# P05_Processor_Page_3_of_3.net
KiCad netlist of a schematic drawn in Altium Designer
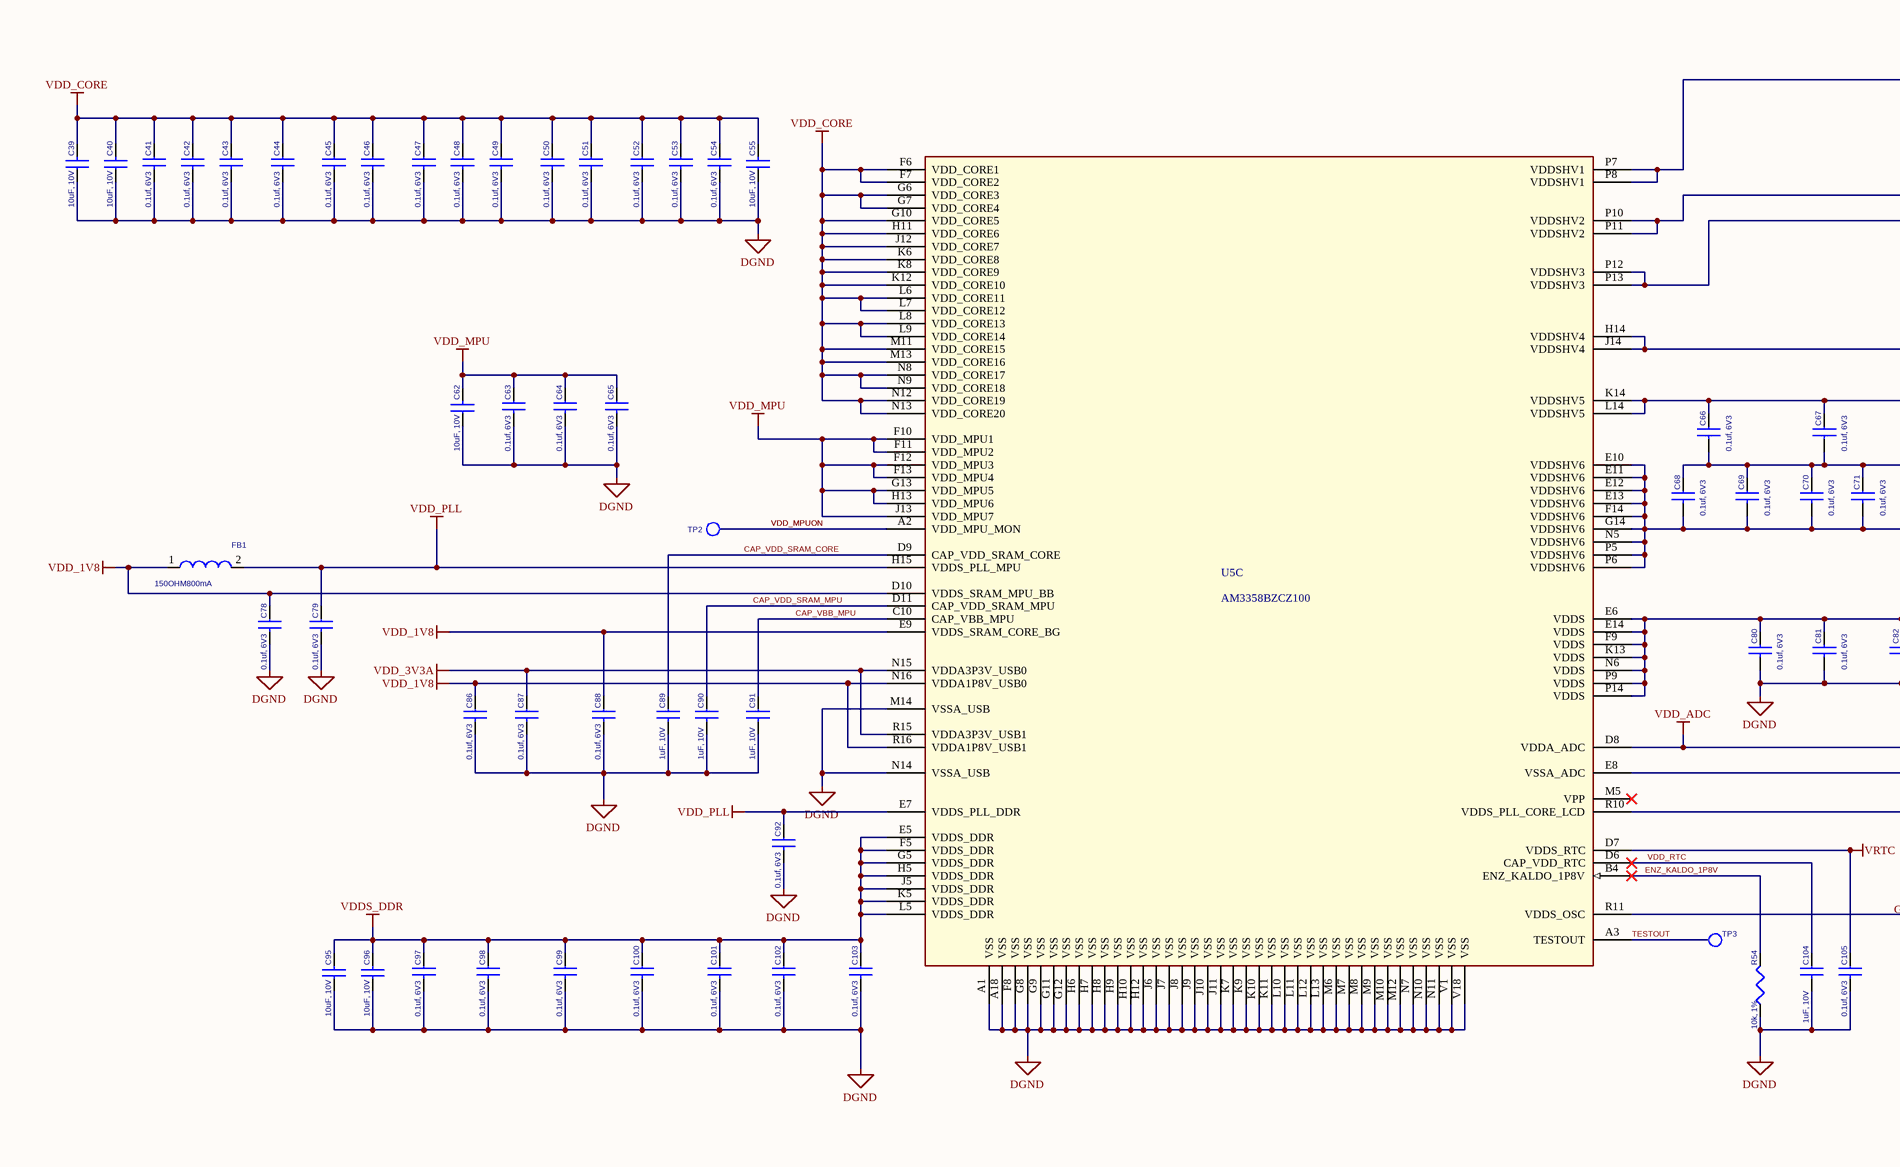
[diagram p0: P05_Processor Page 3 of 3.SchDoc, left]
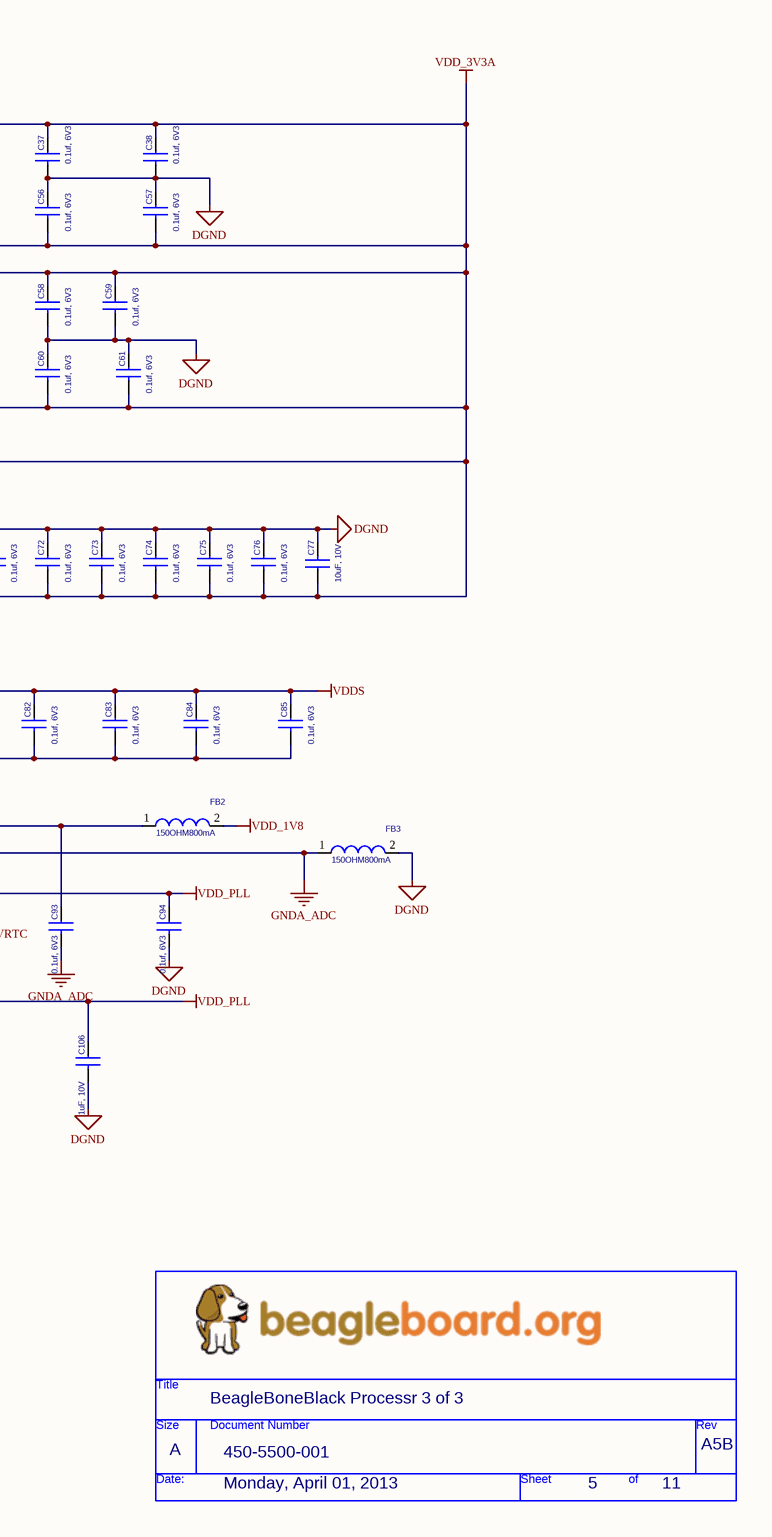
[diagram p1: P05_Processor Page 3 of 3.SchDoc, right]

(export (version "E")
  (design (tool "Eeschema 10.0.6"))
  (components
    (comp (ref "C37")
      (value "0.1uf, 6V3")
      (footprint "402")
      (description "CAP CER 0.1UF 6.3V 10% X5R 0402")
      (fields
        (field (name "MANUFACTURER") "TDK Corporation")
        (field (name "MANUFACTURER PART NUMBER") "C1005X5R0J104K050BA")
      )
      (libsource (lib "BEAGLEBONEBLACK_REV A5B") (part "CAP_0.1uF_X7R_16V_10% 0402"))
    )
    (comp (ref "C38")
      (value "0.1uf, 6V3")
      (footprint "402")
      (description "CAP CER 0.1UF 6.3V 10% X5R 0402")
      (fields
        (field (name "MANUFACTURER") "TDK Corporation")
        (field (name "MANUFACTURER PART NUMBER") "C1005X5R0J104K050BA")
      )
      (libsource (lib "BEAGLEBONEBLACK_REV A5B") (part "CAP_0.1uF_X7R_16V_10% 0402"))
    )
    (comp (ref "C39")
      (value "10uF, 10V")
      (description "CAP CER 10UF 10V Y5V 0805")
      (fields
        (field (name "MANUFACTURER") "TDK Corporation")
        (field (name "MANUFACTURER PART NUMBER") "C2012Y5V1A106Z")
      )
      (libsource (lib "BEAGLEBONEBLACK_REV A5B") (part "CAP_10uF_Y5V_10V_10%_0805"))
    )
    (comp (ref "C40")
      (value "10uF, 10V")
      (description "CAP CER 10UF 10V Y5V 0805")
      (fields
        (field (name "MANUFACTURER") "TDK Corporation")
        (field (name "MANUFACTURER PART NUMBER") "C2012Y5V1A106Z")
      )
      (libsource (lib "BEAGLEBONEBLACK_REV A5B") (part "CAP_10uF_Y5V_10V_10%_0805"))
    )
    (comp (ref "C41")
      (value "0.1uf, 6V3")
      (footprint "402")
      (description "CAP CER 0.1UF 6.3V 10% X5R 0402")
      (fields
        (field (name "MANUFACTURER") "TDK Corporation")
        (field (name "MANUFACTURER PART NUMBER") "C1005X5R0J104K050BA")
      )
      (libsource (lib "BEAGLEBONEBLACK_REV A5B") (part "CAP_0.1uF_X7R_16V_10% 0402"))
    )
    (comp (ref "C42")
      (value "0.1uf, 6V3")
      (footprint "402")
      (description "CAP CER 0.1UF 6.3V 10% X5R 0402")
      (fields
        (field (name "MANUFACTURER") "TDK Corporation")
        (field (name "MANUFACTURER PART NUMBER") "C1005X5R0J104K050BA")
      )
      (libsource (lib "BEAGLEBONEBLACK_REV A5B") (part "CAP_0.1uF_X7R_16V_10% 0402"))
    )
    (comp (ref "C43")
      (value "0.1uf, 6V3")
      (footprint "402")
      (description "CAP CER 0.1UF 6.3V 10% X5R 0402")
      (fields
        (field (name "MANUFACTURER") "TDK Corporation")
        (field (name "MANUFACTURER PART NUMBER") "C1005X5R0J104K050BA")
      )
      (libsource (lib "BEAGLEBONEBLACK_REV A5B") (part "CAP_0.1uF_X7R_16V_10% 0402"))
    )
    (comp (ref "C44")
      (value "0.1uf, 6V3")
      (footprint "402")
      (description "CAP CER 0.1UF 6.3V 10% X5R 0402")
      (fields
        (field (name "MANUFACTURER") "TDK Corporation")
        (field (name "MANUFACTURER PART NUMBER") "C1005X5R0J104K050BA")
      )
      (libsource (lib "BEAGLEBONEBLACK_REV A5B") (part "CAP_0.1uF_X7R_16V_10% 0402"))
    )
    (comp (ref "C45")
      (value "0.1uf, 6V3")
      (footprint "402")
      (description "CAP CER 0.1UF 6.3V 10% X5R 0402")
      (fields
        (field (name "MANUFACTURER") "TDK Corporation")
        (field (name "MANUFACTURER PART NUMBER") "C1005X5R0J104K050BA")
      )
      (libsource (lib "BEAGLEBONEBLACK_REV A5B") (part "CAP_0.1uF_X7R_16V_10% 0402"))
    )
    (comp (ref "C46")
      (value "0.1uf, 6V3")
      (footprint "402")
      (description "CAP CER 0.1UF 6.3V 10% X5R 0402")
      (fields
        (field (name "MANUFACTURER") "TDK Corporation")
        (field (name "MANUFACTURER PART NUMBER") "C1005X5R0J104K050BA")
      )
      (libsource (lib "BEAGLEBONEBLACK_REV A5B") (part "CAP_0.1uF_X7R_16V_10% 0402"))
    )
    (comp (ref "C47")
      (value "0.1uf, 6V3")
      (footprint "402")
      (description "CAP CER 0.1UF 6.3V 10% X5R 0402")
      (fields
        (field (name "MANUFACTURER") "TDK Corporation")
        (field (name "MANUFACTURER PART NUMBER") "C1005X5R0J104K050BA")
      )
      (libsource (lib "BEAGLEBONEBLACK_REV A5B") (part "CAP_0.1uF_X7R_16V_10% 0402"))
    )
    (comp (ref "C48")
      (value "0.1uf, 6V3")
      (footprint "402")
      (description "CAP CER 0.1UF 6.3V 10% X5R 0402")
      (fields
        (field (name "MANUFACTURER") "TDK Corporation")
        (field (name "MANUFACTURER PART NUMBER") "C1005X5R0J104K050BA")
      )
      (libsource (lib "BEAGLEBONEBLACK_REV A5B") (part "CAP_0.1uF_X7R_16V_10% 0402"))
    )
    (comp (ref "C49")
      (value "0.1uf, 6V3")
      (footprint "402")
      (description "CAP CER 0.1UF 6.3V 10% X5R 0402")
      (fields
        (field (name "MANUFACTURER") "TDK Corporation")
        (field (name "MANUFACTURER PART NUMBER") "C1005X5R0J104K050BA")
      )
      (libsource (lib "BEAGLEBONEBLACK_REV A5B") (part "CAP_0.1uF_X7R_16V_10% 0402"))
    )
    (comp (ref "C50")
      (value "0.1uf, 6V3")
      (footprint "402")
      (description "CAP CER 0.1UF 6.3V 10% X5R 0402")
      (fields
        (field (name "MANUFACTURER") "TDK Corporation")
        (field (name "MANUFACTURER PART NUMBER") "C1005X5R0J104K050BA")
      )
      (libsource (lib "BEAGLEBONEBLACK_REV A5B") (part "CAP_0.1uF_X7R_16V_10% 0402"))
    )
    (comp (ref "C51")
      (value "0.1uf, 6V3")
      (footprint "402")
      (description "CAP CER 0.1UF 6.3V 10% X5R 0402")
      (fields
        (field (name "MANUFACTURER") "TDK Corporation")
        (field (name "MANUFACTURER PART NUMBER") "C1005X5R0J104K050BA")
      )
      (libsource (lib "BEAGLEBONEBLACK_REV A5B") (part "CAP_0.1uF_X7R_16V_10% 0402"))
    )
    (comp (ref "C52")
      (value "0.1uf, 6V3")
      (footprint "402")
      (description "CAP CER 0.1UF 6.3V 10% X5R 0402")
      (fields
        (field (name "MANUFACTURER") "TDK Corporation")
        (field (name "MANUFACTURER PART NUMBER") "C1005X5R0J104K050BA")
      )
      (libsource (lib "BEAGLEBONEBLACK_REV A5B") (part "CAP_0.1uF_X7R_16V_10% 0402"))
    )
    (comp (ref "C53")
      (value "0.1uf, 6V3")
      (footprint "402")
      (description "CAP CER 0.1UF 6.3V 10% X5R 0402")
      (fields
        (field (name "MANUFACTURER") "TDK Corporation")
        (field (name "MANUFACTURER PART NUMBER") "C1005X5R0J104K050BA")
      )
      (libsource (lib "BEAGLEBONEBLACK_REV A5B") (part "CAP_0.1uF_X7R_16V_10% 0402"))
    )
    (comp (ref "C54")
      (value "0.1uf, 6V3")
      (footprint "402")
      (description "CAP CER 0.1UF 6.3V 10% X5R 0402")
      (fields
        (field (name "MANUFACTURER") "TDK Corporation")
        (field (name "MANUFACTURER PART NUMBER") "C1005X5R0J104K050BA")
      )
      (libsource (lib "BEAGLEBONEBLACK_REV A5B") (part "CAP_0.1uF_X7R_16V_10% 0402"))
    )
    (comp (ref "C55")
      (value "10uF, 10V")
      (description "CAP CER 10UF 10V Y5V 0805")
      (fields
        (field (name "MANUFACTURER") "TDK Corporation")
        (field (name "MANUFACTURER PART NUMBER") "C2012Y5V1A106Z")
      )
      (libsource (lib "BEAGLEBONEBLACK_REV A5B") (part "CAP_10uF_Y5V_10V_10%_0805"))
    )
    (comp (ref "C56")
      (value "0.1uf, 6V3")
      (footprint "402")
      (description "CAP CER 0.1UF 6.3V 10% X5R 0402")
      (fields
        (field (name "MANUFACTURER") "TDK Corporation")
        (field (name "MANUFACTURER PART NUMBER") "C1005X5R0J104K050BA")
      )
      (libsource (lib "BEAGLEBONEBLACK_REV A5B") (part "CAP_0.1uF_X7R_16V_10% 0402"))
    )
    (comp (ref "C57")
      (value "0.1uf, 6V3")
      (footprint "402")
      (description "CAP CER 0.1UF 6.3V 10% X5R 0402")
      (fields
        (field (name "MANUFACTURER") "TDK Corporation")
        (field (name "MANUFACTURER PART NUMBER") "C1005X5R0J104K050BA")
      )
      (libsource (lib "BEAGLEBONEBLACK_REV A5B") (part "CAP_0.1uF_X7R_16V_10% 0402"))
    )
    (comp (ref "C58")
      (value "0.1uf, 6V3")
      (footprint "402")
      (description "CAP CER 0.1UF 6.3V 10% X5R 0402")
      (fields
        (field (name "MANUFACTURER") "TDK Corporation")
        (field (name "MANUFACTURER PART NUMBER") "C1005X5R0J104K050BA")
      )
      (libsource (lib "BEAGLEBONEBLACK_REV A5B") (part "CAP_0.1uF_X7R_16V_10% 0402"))
    )
    (comp (ref "C59")
      (value "0.1uf, 6V3")
      (footprint "402")
      (description "CAP CER 0.1UF 6.3V 10% X5R 0402")
      (fields
        (field (name "MANUFACTURER") "TDK Corporation")
        (field (name "MANUFACTURER PART NUMBER") "C1005X5R0J104K050BA")
      )
      (libsource (lib "BEAGLEBONEBLACK_REV A5B") (part "CAP_0.1uF_X7R_16V_10% 0402"))
    )
    (comp (ref "C60")
      (value "0.1uf, 6V3")
      (footprint "402")
      (description "CAP CER 0.1UF 6.3V 10% X5R 0402")
      (fields
        (field (name "MANUFACTURER") "TDK Corporation")
        (field (name "MANUFACTURER PART NUMBER") "C1005X5R0J104K050BA")
      )
      (libsource (lib "BEAGLEBONEBLACK_REV A5B") (part "CAP_0.1uF_X7R_16V_10% 0402"))
    )
    (comp (ref "C61")
      (value "0.1uf, 6V3")
      (footprint "402")
      (description "CAP CER 0.1UF 6.3V 10% X5R 0402")
      (fields
        (field (name "MANUFACTURER") "TDK Corporation")
        (field (name "MANUFACTURER PART NUMBER") "C1005X5R0J104K050BA")
      )
      (libsource (lib "BEAGLEBONEBLACK_REV A5B") (part "CAP_0.1uF_X7R_16V_10% 0402"))
    )
    (comp (ref "C62")
      (value "10uF, 10V")
      (description "CAP CER 10UF 10V Y5V 0805")
      (fields
        (field (name "MANUFACTURER") "TDK Corporation")
        (field (name "MANUFACTURER PART NUMBER") "C2012Y5V1A106Z")
      )
      (libsource (lib "BEAGLEBONEBLACK_REV A5B") (part "CAP_10uF_Y5V_10V_10%_0805"))
    )
    (comp (ref "C63")
      (value "0.1uf, 6V3")
      (footprint "402")
      (description "CAP CER 0.1UF 6.3V 10% X5R 0402")
      (fields
        (field (name "MANUFACTURER") "TDK Corporation")
        (field (name "MANUFACTURER PART NUMBER") "C1005X5R0J104K050BA")
      )
      (libsource (lib "BEAGLEBONEBLACK_REV A5B") (part "CAP_0.1uF_X7R_16V_10% 0402"))
    )
    (comp (ref "C64")
      (value "0.1uf, 6V3")
      (footprint "402")
      (description "CAP CER 0.1UF 6.3V 10% X5R 0402")
      (fields
        (field (name "MANUFACTURER") "TDK Corporation")
        (field (name "MANUFACTURER PART NUMBER") "C1005X5R0J104K050BA")
      )
      (libsource (lib "BEAGLEBONEBLACK_REV A5B") (part "CAP_0.1uF_X7R_16V_10% 0402"))
    )
    (comp (ref "C65")
      (value "0.1uf, 6V3")
      (footprint "402")
      (description "CAP CER 0.1UF 6.3V 10% X5R 0402")
      (fields
        (field (name "MANUFACTURER") "TDK Corporation")
        (field (name "MANUFACTURER PART NUMBER") "C1005X5R0J104K050BA")
      )
      (libsource (lib "BEAGLEBONEBLACK_REV A5B") (part "CAP_0.1uF_X7R_16V_10% 0402"))
    )
    (comp (ref "C66")
      (value "0.1uf, 6V3")
      (footprint "402")
      (description "CAP CER 0.1UF 6.3V 10% X5R 0402")
      (fields
        (field (name "MANUFACTURER") "TDK Corporation")
        (field (name "MANUFACTURER PART NUMBER") "C1005X5R0J104K050BA")
      )
      (libsource (lib "BEAGLEBONEBLACK_REV A5B") (part "CAP_0.1uF_X7R_16V_10% 0402"))
    )
    (comp (ref "C67")
      (value "0.1uf, 6V3")
      (footprint "402")
      (description "CAP CER 0.1UF 6.3V 10% X5R 0402")
      (fields
        (field (name "MANUFACTURER") "TDK Corporation")
        (field (name "MANUFACTURER PART NUMBER") "C1005X5R0J104K050BA")
      )
      (libsource (lib "BEAGLEBONEBLACK_REV A5B") (part "CAP_0.1uF_X7R_16V_10% 0402"))
    )
    (comp (ref "C68")
      (value "0.1uf, 6V3")
      (footprint "402")
      (description "CAP CER 0.1UF 6.3V 10% X5R 0402")
      (fields
        (field (name "MANUFACTURER") "TDK Corporation")
        (field (name "MANUFACTURER PART NUMBER") "C1005X5R0J104K050BA")
      )
      (libsource (lib "BEAGLEBONEBLACK_REV A5B") (part "CAP_0.1uF_X7R_16V_10% 0402"))
    )
    (comp (ref "C69")
      (value "0.1uf, 6V3")
      (footprint "402")
      (description "CAP CER 0.1UF 6.3V 10% X5R 0402")
      (fields
        (field (name "MANUFACTURER") "TDK Corporation")
        (field (name "MANUFACTURER PART NUMBER") "C1005X5R0J104K050BA")
      )
      (libsource (lib "BEAGLEBONEBLACK_REV A5B") (part "CAP_0.1uF_X7R_16V_10% 0402"))
    )
    (comp (ref "C70")
      (value "0.1uf, 6V3")
      (footprint "402")
      (description "CAP CER 0.1UF 6.3V 10% X5R 0402")
      (fields
        (field (name "MANUFACTURER") "TDK Corporation")
        (field (name "MANUFACTURER PART NUMBER") "C1005X5R0J104K050BA")
      )
      (libsource (lib "BEAGLEBONEBLACK_REV A5B") (part "CAP_0.1uF_X7R_16V_10% 0402"))
    )
    (comp (ref "C71")
      (value "0.1uf, 6V3")
      (footprint "402")
      (description "CAP CER 0.1UF 6.3V 10% X5R 0402")
      (fields
        (field (name "MANUFACTURER") "TDK Corporation")
        (field (name "MANUFACTURER PART NUMBER") "C1005X5R0J104K050BA")
      )
      (libsource (lib "BEAGLEBONEBLACK_REV A5B") (part "CAP_0.1uF_X7R_16V_10% 0402"))
    )
    (comp (ref "C72")
      (value "0.1uf, 6V3")
      (footprint "402")
      (description "CAP CER 0.1UF 6.3V 10% X5R 0402")
      (fields
        (field (name "MANUFACTURER") "TDK Corporation")
        (field (name "MANUFACTURER PART NUMBER") "C1005X5R0J104K050BA")
      )
      (libsource (lib "BEAGLEBONEBLACK_REV A5B") (part "CAP_0.1uF_X7R_16V_10% 0402"))
    )
    (comp (ref "C73")
      (value "0.1uf, 6V3")
      (footprint "402")
      (description "CAP CER 0.1UF 6.3V 10% X5R 0402")
      (fields
        (field (name "MANUFACTURER") "TDK Corporation")
        (field (name "MANUFACTURER PART NUMBER") "C1005X5R0J104K050BA")
      )
      (libsource (lib "BEAGLEBONEBLACK_REV A5B") (part "CAP_0.1uF_X7R_16V_10% 0402"))
    )
    (comp (ref "C74")
      (value "0.1uf, 6V3")
      (footprint "402")
      (description "CAP CER 0.1UF 6.3V 10% X5R 0402")
      (fields
        (field (name "MANUFACTURER") "TDK Corporation")
        (field (name "MANUFACTURER PART NUMBER") "C1005X5R0J104K050BA")
      )
      (libsource (lib "BEAGLEBONEBLACK_REV A5B") (part "CAP_0.1uF_X7R_16V_10% 0402"))
    )
    (comp (ref "C75")
      (value "0.1uf, 6V3")
      (footprint "402")
      (description "CAP CER 0.1UF 6.3V 10% X5R 0402")
      (fields
        (field (name "MANUFACTURER") "TDK Corporation")
        (field (name "MANUFACTURER PART NUMBER") "C1005X5R0J104K050BA")
      )
      (libsource (lib "BEAGLEBONEBLACK_REV A5B") (part "CAP_0.1uF_X7R_16V_10% 0402"))
    )
    (comp (ref "C76")
      (value "0.1uf, 6V3")
      (footprint "402")
      (description "CAP CER 0.1UF 6.3V 10% X5R 0402")
      (fields
        (field (name "MANUFACTURER") "TDK Corporation")
        (field (name "MANUFACTURER PART NUMBER") "C1005X5R0J104K050BA")
      )
      (libsource (lib "BEAGLEBONEBLACK_REV A5B") (part "CAP_0.1uF_X7R_16V_10% 0402"))
    )
    (comp (ref "C77")
      (value "10uF, 10V")
      (description "CAP CER 10UF 10V Y5V 0805")
      (fields
        (field (name "MANUFACTURER") "TDK Corporation")
        (field (name "MANUFACTURER PART NUMBER") "C2012Y5V1A106Z")
      )
      (libsource (lib "BEAGLEBONEBLACK_REV A5B") (part "CAP_10uF_Y5V_10V_10%_0805"))
    )
    (comp (ref "C78")
      (value "0.1uf, 6V3")
      (footprint "402")
      (description "CAP CER 0.1UF 6.3V 10% X5R 0402")
      (fields
        (field (name "MANUFACTURER") "TDK Corporation")
        (field (name "MANUFACTURER PART NUMBER") "C1005X5R0J104K050BA")
      )
      (libsource (lib "BEAGLEBONEBLACK_REV A5B") (part "CAP_0.1uF_X7R_16V_10% 0402"))
    )
    (comp (ref "C79")
      (value "0.1uf, 6V3")
      (footprint "402")
      (description "CAP CER 0.1UF 6.3V 10% X5R 0402")
      (fields
        (field (name "MANUFACTURER") "TDK Corporation")
        (field (name "MANUFACTURER PART NUMBER") "C1005X5R0J104K050BA")
      )
      (libsource (lib "BEAGLEBONEBLACK_REV A5B") (part "CAP_0.1uF_X7R_16V_10% 0402"))
    )
    (comp (ref "C80")
      (value "0.1uf, 6V3")
      (footprint "402")
      (description "CAP CER 0.1UF 6.3V 10% X5R 0402")
      (fields
        (field (name "MANUFACTURER") "TDK Corporation")
        (field (name "MANUFACTURER PART NUMBER") "C1005X5R0J104K050BA")
      )
      (libsource (lib "BEAGLEBONEBLACK_REV A5B") (part "CAP_0.1uF_X7R_16V_10% 0402"))
    )
    (comp (ref "C81")
      (value "0.1uf, 6V3")
      (footprint "402")
      (description "CAP CER 0.1UF 6.3V 10% X5R 0402")
      (fields
        (field (name "MANUFACTURER") "TDK Corporation")
        (field (name "MANUFACTURER PART NUMBER") "C1005X5R0J104K050BA")
      )
      (libsource (lib "BEAGLEBONEBLACK_REV A5B") (part "CAP_0.1uF_X7R_16V_10% 0402"))
    )
    (comp (ref "C82")
      (value "0.1uf, 6V3")
      (footprint "402")
      (description "CAP CER 0.1UF 6.3V 10% X5R 0402")
      (fields
        (field (name "MANUFACTURER") "TDK Corporation")
        (field (name "MANUFACTURER PART NUMBER") "C1005X5R0J104K050BA")
      )
      (libsource (lib "BEAGLEBONEBLACK_REV A5B") (part "CAP_0.1uF_X7R_16V_10% 0402"))
    )
    (comp (ref "C83")
      (value "0.1uf, 6V3")
      (footprint "402")
      (description "CAP CER 0.1UF 6.3V 10% X5R 0402")
      (fields
        (field (name "MANUFACTURER") "TDK Corporation")
        (field (name "MANUFACTURER PART NUMBER") "C1005X5R0J104K050BA")
      )
      (libsource (lib "BEAGLEBONEBLACK_REV A5B") (part "CAP_0.1uF_X7R_16V_10% 0402"))
    )
    (comp (ref "C84")
      (value "0.1uf, 6V3")
      (footprint "402")
      (description "CAP CER 0.1UF 6.3V 10% X5R 0402")
      (fields
        (field (name "MANUFACTURER") "TDK Corporation")
        (field (name "MANUFACTURER PART NUMBER") "C1005X5R0J104K050BA")
      )
      (libsource (lib "BEAGLEBONEBLACK_REV A5B") (part "CAP_0.1uF_X7R_16V_10% 0402"))
    )
    (comp (ref "C85")
      (value "0.1uf, 6V3")
      (footprint "402")
      (description "CAP CER 0.1UF 6.3V 10% X5R 0402")
      (fields
        (field (name "MANUFACTURER") "TDK Corporation")
        (field (name "MANUFACTURER PART NUMBER") "C1005X5R0J104K050BA")
      )
      (libsource (lib "BEAGLEBONEBLACK_REV A5B") (part "CAP_0.1uF_X7R_16V_10% 0402"))
    )
    (comp (ref "C86")
      (value "0.1uf, 6V3")
      (footprint "402")
      (description "CAP CER 0.1UF 6.3V 10% X5R 0402")
      (fields
        (field (name "MANUFACTURER") "TDK Corporation")
        (field (name "MANUFACTURER PART NUMBER") "C1005X5R0J104K050BA")
      )
      (libsource (lib "BEAGLEBONEBLACK_REV A5B") (part "CAP_0.1uF_X7R_16V_10% 0402"))
    )
    (comp (ref "C87")
      (value "0.1uf, 6V3")
      (footprint "402")
      (description "CAP CER 0.1UF 6.3V 10% X5R 0402")
      (fields
        (field (name "MANUFACTURER") "TDK Corporation")
        (field (name "MANUFACTURER PART NUMBER") "C1005X5R0J104K050BA")
      )
      (libsource (lib "BEAGLEBONEBLACK_REV A5B") (part "CAP_0.1uF_X7R_16V_10% 0402"))
    )
    (comp (ref "C88")
      (value "0.1uf, 6V3")
      (footprint "402")
      (description "CAP CER 0.1UF 6.3V 10% X5R 0402")
      (fields
        (field (name "MANUFACTURER") "TDK Corporation")
        (field (name "MANUFACTURER PART NUMBER") "C1005X5R0J104K050BA")
      )
      (libsource (lib "BEAGLEBONEBLACK_REV A5B") (part "CAP_0.1uF_X7R_16V_10% 0402"))
    )
    (comp (ref "C89")
      (value "1uF, 10V")
      (footprint "402")
      (description "CAP CER 1UF 10V 10% X5R 0402")
      (fields
        (field (name "MANUFACTURER") "AVX Corporation")
        (field (name "MANUFACTURER PART NUMBER") "0402ZD105KAT2A")
      )
      (libsource (lib "BEAGLEBONEBLACK_REV A5B") (part "CAP_1.0UF_X5R_10V_10%_0402"))
    )
    (comp (ref "C90")
      (value "1uF, 10V")
      (footprint "402")
      (description "CAP CER 1UF 10V 10% X5R 0402")
      (fields
        (field (name "MANUFACTURER") "AVX Corporation")
        (field (name "MANUFACTURER PART NUMBER") "0402ZD105KAT2A")
      )
      (libsource (lib "BEAGLEBONEBLACK_REV A5B") (part "CAP_1.0UF_X5R_10V_10%_0402"))
    )
    (comp (ref "C91")
      (value "1uF, 10V")
      (footprint "402")
      (description "CAP CER 1UF 10V 10% X5R 0402")
      (fields
        (field (name "MANUFACTURER") "AVX Corporation")
        (field (name "MANUFACTURER PART NUMBER") "0402ZD105KAT2A")
      )
      (libsource (lib "BEAGLEBONEBLACK_REV A5B") (part "CAP_1.0UF_X5R_10V_10%_0402"))
    )
    (comp (ref "C92")
      (value "0.1uf, 6V3")
      (footprint "402")
      (description "CAP CER 0.1UF 6.3V 10% X5R 0402")
      (fields
        (field (name "MANUFACTURER") "TDK Corporation")
        (field (name "MANUFACTURER PART NUMBER") "C1005X5R0J104K050BA")
      )
      (libsource (lib "BEAGLEBONEBLACK_REV A5B") (part "CAP_0.1uF_X7R_16V_10% 0402"))
    )
    (comp (ref "C93")
      (value "0.1uf, 6V3")
      (footprint "402")
      (description "CAP CER 0.1UF 6.3V 10% X5R 0402")
      (fields
        (field (name "MANUFACTURER") "TDK Corporation")
        (field (name "MANUFACTURER PART NUMBER") "C1005X5R0J104K050BA")
      )
      (libsource (lib "BEAGLEBONEBLACK_REV A5B") (part "CAP_0.1uF_X7R_16V_10% 0402"))
    )
    (comp (ref "C94")
      (value "0.1uf, 6V3")
      (footprint "402")
      (description "CAP CER 0.1UF 6.3V 10% X5R 0402")
      (fields
        (field (name "MANUFACTURER") "TDK Corporation")
        (field (name "MANUFACTURER PART NUMBER") "C1005X5R0J104K050BA")
      )
      (libsource (lib "BEAGLEBONEBLACK_REV A5B") (part "CAP_0.1uF_X7R_16V_10% 0402"))
    )
    (comp (ref "C95")
      (value "10uF, 10V")
      (description "CAP CER 10UF 10V Y5V 0805")
      (fields
        (field (name "MANUFACTURER") "TDK Corporation")
        (field (name "MANUFACTURER PART NUMBER") "C2012Y5V1A106Z")
      )
      (libsource (lib "BEAGLEBONEBLACK_REV A5B") (part "CAP_10uF_Y5V_10V_10%_0805"))
    )
    (comp (ref "C96")
      (value "10uF, 10V")
      (description "CAP CER 10UF 10V Y5V 0805")
      (fields
        (field (name "MANUFACTURER") "TDK Corporation")
        (field (name "MANUFACTURER PART NUMBER") "C2012Y5V1A106Z")
      )
      (libsource (lib "BEAGLEBONEBLACK_REV A5B") (part "CAP_10uF_Y5V_10V_10%_0805"))
    )
    (comp (ref "C97")
      (value "0.1uf, 6V3")
      (footprint "402")
      (description "CAP CER 0.1UF 6.3V 10% X5R 0402")
      (fields
        (field (name "MANUFACTURER") "TDK Corporation")
        (field (name "MANUFACTURER PART NUMBER") "C1005X5R0J104K050BA")
      )
      (libsource (lib "BEAGLEBONEBLACK_REV A5B") (part "CAP_0.1uF_X7R_16V_10% 0402"))
    )
    (comp (ref "C98")
      (value "0.1uf, 6V3")
      (footprint "402")
      (description "CAP CER 0.1UF 6.3V 10% X5R 0402")
      (fields
        (field (name "MANUFACTURER") "TDK Corporation")
        (field (name "MANUFACTURER PART NUMBER") "C1005X5R0J104K050BA")
      )
      (libsource (lib "BEAGLEBONEBLACK_REV A5B") (part "CAP_0.1uF_X7R_16V_10% 0402"))
    )
    (comp (ref "C99")
      (value "0.1uf, 6V3")
      (footprint "402")
      (description "CAP CER 0.1UF 6.3V 10% X5R 0402")
      (fields
        (field (name "MANUFACTURER") "TDK Corporation")
        (field (name "MANUFACTURER PART NUMBER") "C1005X5R0J104K050BA")
      )
      (libsource (lib "BEAGLEBONEBLACK_REV A5B") (part "CAP_0.1uF_X7R_16V_10% 0402"))
    )
    (comp (ref "C100")
      (value "0.1uf, 6V3")
      (footprint "402")
      (description "CAP CER 0.1UF 6.3V 10% X5R 0402")
      (fields
        (field (name "MANUFACTURER") "TDK Corporation")
        (field (name "MANUFACTURER PART NUMBER") "C1005X5R0J104K050BA")
      )
      (libsource (lib "BEAGLEBONEBLACK_REV A5B") (part "CAP_0.1uF_X7R_16V_10% 0402"))
    )
    (comp (ref "C101")
      (value "0.1uf, 6V3")
      (footprint "402")
      (description "CAP CER 0.1UF 6.3V 10% X5R 0402")
      (fields
        (field (name "MANUFACTURER") "TDK Corporation")
        (field (name "MANUFACTURER PART NUMBER") "C1005X5R0J104K050BA")
      )
      (libsource (lib "BEAGLEBONEBLACK_REV A5B") (part "CAP_0.1uF_X7R_16V_10% 0402"))
    )
    (comp (ref "C102")
      (value "0.1uf, 6V3")
      (footprint "402")
      (description "CAP CER 0.1UF 6.3V 10% X5R 0402")
      (fields
        (field (name "MANUFACTURER") "TDK Corporation")
        (field (name "MANUFACTURER PART NUMBER") "C1005X5R0J104K050BA")
      )
      (libsource (lib "BEAGLEBONEBLACK_REV A5B") (part "CAP_0.1uF_X7R_16V_10% 0402"))
    )
    (comp (ref "C103")
      (value "0.1uf, 6V3")
      (footprint "402")
      (description "CAP CER 0.1UF 6.3V 10% X5R 0402")
      (fields
        (field (name "MANUFACTURER") "TDK Corporation")
        (field (name "MANUFACTURER PART NUMBER") "C1005X5R0J104K050BA")
      )
      (libsource (lib "BEAGLEBONEBLACK_REV A5B") (part "CAP_0.1uF_X7R_16V_10% 0402"))
    )
    (comp (ref "C104")
      (value "1uF, 10V")
      (footprint "402")
      (description "CAP CER 1UF 10V 10% X5R 0402")
      (fields
        (field (name "MANUFACTURER") "AVX Corporation")
        (field (name "MANUFACTURER PART NUMBER") "0402ZD105KAT2A")
      )
      (libsource (lib "BEAGLEBONEBLACK_REV A5B") (part "CAP_1.0UF_X5R_10V_10%_0402"))
    )
    (comp (ref "C105")
      (value "0.1uf, 6V3")
      (footprint "402")
      (description "CAP CER 0.1UF 6.3V 10% X5R 0402")
      (fields
        (field (name "MANUFACTURER") "TDK Corporation")
        (field (name "MANUFACTURER PART NUMBER") "C1005X5R0J104K050BA")
      )
      (libsource (lib "BEAGLEBONEBLACK_REV A5B") (part "CAP_0.1uF_X7R_16V_10% 0402"))
    )
    (comp (ref "C106")
      (value "1uF, 10V")
      (footprint "402")
      (description "CAP CER 1UF 10V 10% X5R 0402")
      (fields
        (field (name "MANUFACTURER") "AVX Corporation")
        (field (name "MANUFACTURER PART NUMBER") "0402ZD105KAT2A")
      )
      (libsource (lib "BEAGLEBONEBLACK_REV A5B") (part "CAP_1.0UF_X5R_10V_10%_0402"))
    )
    (comp (ref "FB1")
      (value "150OHM800mA")
      (footprint "SM-7351-IND-0805")
      (description "FERRITE 800MA 150 OHM 0805 SMD")
      (fields (field (name "MFR") "Steward") (field (name "TIINTPARTNUMBER") "1L0010"))
      (libsource (lib "BEAGLEBONEBLACK_REV A5B") (part "FER_180_200_0"))
    )
    (comp (ref "FB2")
      (value "150OHM800mA")
      (footprint "SM-7351-IND-0805")
      (description "FERRITE 800MA 150 OHM 0805 SMD")
      (fields (field (name "MFR") "Steward") (field (name "TIINTPARTNUMBER") "1L0010"))
      (libsource (lib "BEAGLEBONEBLACK_REV A5B") (part "FER_180_200_0"))
    )
    (comp (ref "FB3")
      (value "150OHM800mA")
      (footprint "SM-7351-IND-0805")
      (description "FERRITE 800MA 150 OHM 0805 SMD")
      (fields (field (name "MFR") "Steward") (field (name "TIINTPARTNUMBER") "1L0010"))
      (libsource (lib "BEAGLEBONEBLACK_REV A5B") (part "FER_180_200_0"))
    )
    (comp (ref "R54")
      (value "10k, 1%")
      (footprint "402")
      (description "RES 10K OHM 1/16W 5% 0402 SMD")
      (fields
        (field (name "MANUFACTURER") "Rohm Semiconductor")
        (field (name "MANUFACTURER PART NUMBER") "MCR01MZPJ103")
      )
      (libsource (lib "BEAGLEBONEBLACK_REV A5B") (part "RES_10K_1/16W_1%_0402"))
    )
    (comp (ref "TP2") (value "TESTPT1") (libsource (lib "BEAGLEBONEBLACK_REV A5B") (part "TESTPT1")))
    (comp (ref "TP3") (value "TESTPT1") (libsource (lib "BEAGLEBONEBLACK_REV A5B") (part "TESTPT1")))
    (comp (ref "U5")
      (value "AM3358BZCZ100")
      (footprint "am33xx_15x15")
      (description "IC MPU SITARA 1.0GHZ 324NFBGA")
      (fields (field (name "MFR") "TI") (field (name "TIINTPARTNUMBER") "1A0242"))
      (libsource (lib "BEAGLEBONEBLACK_REV A5B") (part "IC_AM335X_ZCE_1"))
    )
  )
  (nets
    (net (code "1") (name "/CAP_VBB_MPU") (class "Default")
      (node (ref "C91") (pin "1") (pinfunction "1_1") (pintype "passive"))
      (node (ref "U5") (pin "C10") (pinfunction "CAP_VBB_MPU_C10") (pintype "passive"))
    )
    (net (code "2") (name "/CAP_VDD_SRAM_CORE") (class "Default")
      (node (ref "C89") (pin "1") (pinfunction "1_1") (pintype "passive"))
      (node (ref "U5") (pin "D9") (pinfunction "CAP_VDD_SRAM_CORE_D9") (pintype "power_in"))
    )
    (net (code "3") (name "/CAP_VDD_SRAM_MPU") (class "Default")
      (node (ref "C90") (pin "1") (pinfunction "1_1") (pintype "passive"))
      (node (ref "U5") (pin "D11") (pinfunction "CAP_VDD_SRAM_MPU_D11") (pintype "power_in"))
    )
    (net (code "4") (name "/ENZ_KALDO_1P8V") (class "Default")
      (node (ref "R54") (pin "2") (pinfunction "2_2") (pintype "passive"))
      (node (ref "U5") (pin "B4") (pinfunction "ENZ_KALDO_1P8V_B4") (pintype "input"))
    )
    (net (code "5") (name "/TESTOUT") (class "Default")
      (node (ref "TP3") (pin "1") (pinfunction "TP_1") (pintype "passive"))
      (node (ref "U5") (pin "A3") (pinfunction "TESTOUT_A3") (pintype "passive"))
    )
    (net (code "6") (name "/VDD_MPUON") (class "Default")
      (node (ref "TP2") (pin "1") (pinfunction "TP_1") (pintype "passive"))
      (node (ref "U5") (pin "A2") (pinfunction "VDD_MPU_MON_A2") (pintype "passive"))
    )
    (net (code "7") (name "/VDD_RTC") (class "Default")
      (node (ref "C104") (pin "1") (pinfunction "1_1") (pintype "passive"))
      (node (ref "U5") (pin "D6") (pinfunction "CAP_VDD_RTC_D6") (pintype "power_in"))
    )
    (net (code "8") (name "DGND") (class "Default")
      (node (ref "C100") (pin "2") (pinfunction "2_2") (pintype "passive"))
      (node (ref "C101") (pin "2") (pinfunction "2_2") (pintype "passive"))
      (node (ref "C102") (pin "2") (pinfunction "2_2") (pintype "passive"))
      (node (ref "C103") (pin "2") (pinfunction "2_2") (pintype "passive"))
      (node (ref "C104") (pin "2") (pinfunction "2_2") (pintype "passive"))
      (node (ref "C105") (pin "2") (pinfunction "2_2") (pintype "passive"))
      (node (ref "C106") (pin "2") (pinfunction "2_2") (pintype "passive"))
      (node (ref "C37") (pin "2") (pinfunction "2_2") (pintype "passive"))
      (node (ref "C38") (pin "2") (pinfunction "2_2") (pintype "passive"))
      (node (ref "C39") (pin "1") (pinfunction "1_1") (pintype "passive"))
      (node (ref "C40") (pin "1") (pinfunction "1_1") (pintype "passive"))
      (node (ref "C41") (pin "2") (pinfunction "2_2") (pintype "passive"))
      (node (ref "C42") (pin "2") (pinfunction "2_2") (pintype "passive"))
      (node (ref "C43") (pin "2") (pinfunction "2_2") (pintype "passive"))
      (node (ref "C44") (pin "2") (pinfunction "2_2") (pintype "passive"))
      (node (ref "C45") (pin "2") (pinfunction "2_2") (pintype "passive"))
      (node (ref "C46") (pin "2") (pinfunction "2_2") (pintype "passive"))
      (node (ref "C47") (pin "2") (pinfunction "2_2") (pintype "passive"))
      (node (ref "C48") (pin "2") (pinfunction "2_2") (pintype "passive"))
      (node (ref "C49") (pin "2") (pinfunction "2_2") (pintype "passive"))
      (node (ref "C50") (pin "2") (pinfunction "2_2") (pintype "passive"))
      (node (ref "C51") (pin "2") (pinfunction "2_2") (pintype "passive"))
      (node (ref "C52") (pin "2") (pinfunction "2_2") (pintype "passive"))
      (node (ref "C53") (pin "2") (pinfunction "2_2") (pintype "passive"))
      (node (ref "C54") (pin "2") (pinfunction "2_2") (pintype "passive"))
      (node (ref "C55") (pin "1") (pinfunction "1_1") (pintype "passive"))
      (node (ref "C56") (pin "1") (pinfunction "1_1") (pintype "passive"))
      (node (ref "C57") (pin "1") (pinfunction "1_1") (pintype "passive"))
      (node (ref "C58") (pin "2") (pinfunction "2_2") (pintype "passive"))
      (node (ref "C59") (pin "2") (pinfunction "2_2") (pintype "passive"))
      (node (ref "C60") (pin "1") (pinfunction "1_1") (pintype "passive"))
      (node (ref "C61") (pin "1") (pinfunction "1_1") (pintype "passive"))
      (node (ref "C62") (pin "1") (pinfunction "1_1") (pintype "passive"))
      (node (ref "C63") (pin "2") (pinfunction "2_2") (pintype "passive"))
      (node (ref "C64") (pin "2") (pinfunction "2_2") (pintype "passive"))
      (node (ref "C65") (pin "2") (pinfunction "2_2") (pintype "passive"))
      (node (ref "C66") (pin "2") (pinfunction "2_2") (pintype "passive"))
      (node (ref "C67") (pin "2") (pinfunction "2_2") (pintype "passive"))
      (node (ref "C68") (pin "1") (pinfunction "1_1") (pintype "passive"))
      (node (ref "C69") (pin "1") (pinfunction "1_1") (pintype "passive"))
      (node (ref "C70") (pin "1") (pinfunction "1_1") (pintype "passive"))
      (node (ref "C71") (pin "1") (pinfunction "1_1") (pintype "passive"))
      (node (ref "C72") (pin "1") (pinfunction "1_1") (pintype "passive"))
      (node (ref "C73") (pin "1") (pinfunction "1_1") (pintype "passive"))
      (node (ref "C74") (pin "1") (pinfunction "1_1") (pintype "passive"))
      (node (ref "C75") (pin "1") (pinfunction "1_1") (pintype "passive"))
      (node (ref "C76") (pin "1") (pinfunction "1_1") (pintype "passive"))
      (node (ref "C77") (pin "2") (pinfunction "2_2") (pintype "passive"))
      (node (ref "C78") (pin "2") (pinfunction "2_2") (pintype "passive"))
      (node (ref "C79") (pin "2") (pinfunction "2_2") (pintype "passive"))
      (node (ref "C80") (pin "2") (pinfunction "2_2") (pintype "passive"))
      (node (ref "C81") (pin "2") (pinfunction "2_2") (pintype "passive"))
      (node (ref "C82") (pin "2") (pinfunction "2_2") (pintype "passive"))
      (node (ref "C83") (pin "2") (pinfunction "2_2") (pintype "passive"))
      (node (ref "C84") (pin "2") (pinfunction "2_2") (pintype "passive"))
      (node (ref "C85") (pin "2") (pinfunction "2_2") (pintype "passive"))
      (node (ref "C86") (pin "2") (pinfunction "2_2") (pintype "passive"))
      (node (ref "C87") (pin "2") (pinfunction "2_2") (pintype "passive"))
      (node (ref "C88") (pin "2") (pinfunction "2_2") (pintype "passive"))
      (node (ref "C89") (pin "2") (pinfunction "2_2") (pintype "passive"))
      (node (ref "C90") (pin "2") (pinfunction "2_2") (pintype "passive"))
      (node (ref "C91") (pin "2") (pinfunction "2_2") (pintype "passive"))
      (node (ref "C92") (pin "2") (pinfunction "2_2") (pintype "passive"))
      (node (ref "C94") (pin "2") (pinfunction "2_2") (pintype "passive"))
      (node (ref "C95") (pin "1") (pinfunction "1_1") (pintype "passive"))
      (node (ref "C96") (pin "1") (pinfunction "1_1") (pintype "passive"))
      (node (ref "C97") (pin "2") (pinfunction "2_2") (pintype "passive"))
      (node (ref "C98") (pin "2") (pinfunction "2_2") (pintype "passive"))
      (node (ref "C99") (pin "2") (pinfunction "2_2") (pintype "passive"))
      (node (ref "FB3") (pin "2") (pinfunction "2_2") (pintype "passive"))
      (node (ref "R54") (pin "1") (pinfunction "1_1") (pintype "passive"))
      (node (ref "U5") (pin "A1") (pinfunction "VSS_A1") (pintype "power_in"))
      (node (ref "U5") (pin "A18") (pinfunction "VSS_A18") (pintype "power_in"))
      (node (ref "U5") (pin "F8") (pinfunction "VSS_F8") (pintype "power_in"))
      (node (ref "U5") (pin "G11") (pinfunction "VSS_G11") (pintype "power_in"))
      (node (ref "U5") (pin "G12") (pinfunction "VSS_G12") (pintype "power_in"))
      (node (ref "U5") (pin "G8") (pinfunction "VSS_G8") (pintype "power_in"))
      (node (ref "U5") (pin "G9") (pinfunction "VSS_G9") (pintype "power_in"))
      (node (ref "U5") (pin "H10") (pinfunction "VSS_H10") (pintype "power_in"))
      (node (ref "U5") (pin "H12") (pinfunction "VSS_H12") (pintype "power_in"))
      (node (ref "U5") (pin "H6") (pinfunction "VSS_H6") (pintype "power_in"))
      (node (ref "U5") (pin "H7") (pinfunction "VSS_H7") (pintype "power_in"))
      (node (ref "U5") (pin "H8") (pinfunction "VSS_H8") (pintype "power_in"))
      (node (ref "U5") (pin "H9") (pinfunction "VSS_H9") (pintype "power_in"))
      (node (ref "U5") (pin "J10") (pinfunction "VSS_J10") (pintype "power_in"))
      (node (ref "U5") (pin "J11") (pinfunction "VSS_J11") (pintype "power_in"))
      (node (ref "U5") (pin "J6") (pinfunction "VSS_J6") (pintype "power_in"))
      (node (ref "U5") (pin "J7") (pinfunction "VSS_J7") (pintype "power_in"))
      (node (ref "U5") (pin "J8") (pinfunction "VSS_J8") (pintype "power_in"))
      (node (ref "U5") (pin "J9") (pinfunction "VSS_J9") (pintype "power_in"))
      (node (ref "U5") (pin "K10") (pinfunction "VSS_K10") (pintype "power_in"))
      (node (ref "U5") (pin "K11") (pinfunction "VSS_K11") (pintype "power_in"))
      (node (ref "U5") (pin "K7") (pinfunction "VSS_K7") (pintype "power_in"))
      (node (ref "U5") (pin "K9") (pinfunction "VSS_K9") (pintype "power_in"))
      (node (ref "U5") (pin "L10") (pinfunction "VSS_L10") (pintype "power_in"))
      (node (ref "U5") (pin "L11") (pinfunction "VSS_L11") (pintype "power_in"))
      (node (ref "U5") (pin "L12") (pinfunction "VSS_L12") (pintype "power_in"))
      (node (ref "U5") (pin "L13") (pinfunction "VSS_L13") (pintype "power_in"))
      (node (ref "U5") (pin "M10") (pinfunction "VSS_M10") (pintype "power_in"))
      (node (ref "U5") (pin "M12") (pinfunction "VSS_M12") (pintype "power_in"))
      (node (ref "U5") (pin "M14") (pinfunction "VSSA_USB_M14") (pintype "power_in"))
      (node (ref "U5") (pin "M6") (pinfunction "VSS_M6") (pintype "power_in"))
      (node (ref "U5") (pin "M7") (pinfunction "VSS_M7") (pintype "power_in"))
      (node (ref "U5") (pin "M8") (pinfunction "VSS_M8") (pintype "power_in"))
      (node (ref "U5") (pin "M9") (pinfunction "VSS_M9") (pintype "power_in"))
      (node (ref "U5") (pin "N10") (pinfunction "VSS_N10") (pintype "power_in"))
      (node (ref "U5") (pin "N11") (pinfunction "VSS_N11") (pintype "power_in"))
      (node (ref "U5") (pin "N14") (pinfunction "VSSA_USB_N14") (pintype "power_in"))
      (node (ref "U5") (pin "N7") (pinfunction "VSS_N7") (pintype "power_in"))
      (node (ref "U5") (pin "V1") (pinfunction "VSS_V1") (pintype "power_in"))
      (node (ref "U5") (pin "V18") (pinfunction "VSS_V18") (pintype "power_in"))
    )
    (net (code "9") (name "GNDA_ADC") (class "Default")
      (node (ref "C93") (pin "2") (pinfunction "2_2") (pintype "passive"))
      (node (ref "FB3") (pin "1") (pinfunction "1_1") (pintype "passive"))
      (node (ref "U5") (pin "E8") (pinfunction "VSSA_ADC_E8") (pintype "power_in"))
    )
    (net (code "10") (name "VDDS") (class "Default")
      (node (ref "C80") (pin "1") (pinfunction "1_1") (pintype "passive"))
      (node (ref "C81") (pin "1") (pinfunction "1_1") (pintype "passive"))
      (node (ref "C82") (pin "1") (pinfunction "1_1") (pintype "passive"))
      (node (ref "C83") (pin "1") (pinfunction "1_1") (pintype "passive"))
      (node (ref "C84") (pin "1") (pinfunction "1_1") (pintype "passive"))
      (node (ref "C85") (pin "1") (pinfunction "1_1") (pintype "passive"))
      (node (ref "U5") (pin "E14") (pinfunction "VDDS_E14") (pintype "power_in"))
      (node (ref "U5") (pin "E6") (pinfunction "VDDS_E6") (pintype "power_in"))
      (node (ref "U5") (pin "F9") (pinfunction "VDDS_F9") (pintype "power_in"))
      (node (ref "U5") (pin "K13") (pinfunction "VDDS_K13") (pintype "power_in"))
      (node (ref "U5") (pin "N6") (pinfunction "VDDS_N6") (pintype "power_in"))
      (node (ref "U5") (pin "P14") (pinfunction "VDDS_P14") (pintype "power_in"))
      (node (ref "U5") (pin "P9") (pinfunction "VDDS_P9") (pintype "power_in"))
    )
    (net (code "11") (name "VDDS_DDR") (class "Default")
      (node (ref "C100") (pin "1") (pinfunction "1_1") (pintype "passive"))
      (node (ref "C101") (pin "1") (pinfunction "1_1") (pintype "passive"))
      (node (ref "C102") (pin "1") (pinfunction "1_1") (pintype "passive"))
      (node (ref "C103") (pin "1") (pinfunction "1_1") (pintype "passive"))
      (node (ref "C95") (pin "2") (pinfunction "2_2") (pintype "passive"))
      (node (ref "C96") (pin "2") (pinfunction "2_2") (pintype "passive"))
      (node (ref "C97") (pin "1") (pinfunction "1_1") (pintype "passive"))
      (node (ref "C98") (pin "1") (pinfunction "1_1") (pintype "passive"))
      (node (ref "C99") (pin "1") (pinfunction "1_1") (pintype "passive"))
      (node (ref "U5") (pin "E5") (pinfunction "VDDS_DDR_E5") (pintype "power_in"))
      (node (ref "U5") (pin "F5") (pinfunction "VDDS_DDR_F5") (pintype "power_in"))
      (node (ref "U5") (pin "G5") (pinfunction "VDDS_DDR_G5") (pintype "power_in"))
      (node (ref "U5") (pin "H5") (pinfunction "VDDS_DDR_H5") (pintype "power_in"))
      (node (ref "U5") (pin "J5") (pinfunction "VDDS_DDR_J5") (pintype "power_in"))
      (node (ref "U5") (pin "K5") (pinfunction "VDDS_DDR_K5") (pintype "power_in"))
      (node (ref "U5") (pin "L5") (pinfunction "VDDS_DDR_L5") (pintype "power_in"))
    )
    (net (code "12") (name "VDD_1V8") (class "Default")
      (node (ref "C78") (pin "1") (pinfunction "1_1") (pintype "passive"))
      (node (ref "C86") (pin "1") (pinfunction "1_1") (pintype "passive"))
      (node (ref "C88") (pin "1") (pinfunction "1_1") (pintype "passive"))
      (node (ref "FB1") (pin "1") (pinfunction "1_1") (pintype "passive"))
      (node (ref "FB2") (pin "2") (pinfunction "2_2") (pintype "passive"))
      (node (ref "U5") (pin "D10") (pinfunction "VDDS_SRAM_MPU_BB_D10") (pintype "power_in"))
      (node (ref "U5") (pin "E9") (pinfunction "VDDS_SRAM_CORE_BG_E9") (pintype "power_in"))
      (node (ref "U5") (pin "N16") (pinfunction "VDDA1P8V_USB0_N16") (pintype "power_in"))
      (node (ref "U5") (pin "R16") (pinfunction "VDDA1P8V_USB1_R16") (pintype "power_in"))
    )
    (net (code "13") (name "VDD_3V3A") (class "Default")
      (node (ref "C37") (pin "1") (pinfunction "1_1") (pintype "passive"))
      (node (ref "C38") (pin "1") (pinfunction "1_1") (pintype "passive"))
      (node (ref "C56") (pin "2") (pinfunction "2_2") (pintype "passive"))
      (node (ref "C57") (pin "2") (pinfunction "2_2") (pintype "passive"))
      (node (ref "C58") (pin "1") (pinfunction "1_1") (pintype "passive"))
      (node (ref "C59") (pin "1") (pinfunction "1_1") (pintype "passive"))
      (node (ref "C60") (pin "2") (pinfunction "2_2") (pintype "passive"))
      (node (ref "C61") (pin "2") (pinfunction "2_2") (pintype "passive"))
      (node (ref "C66") (pin "1") (pinfunction "1_1") (pintype "passive"))
      (node (ref "C67") (pin "1") (pinfunction "1_1") (pintype "passive"))
      (node (ref "C68") (pin "2") (pinfunction "2_2") (pintype "passive"))
      (node (ref "C69") (pin "2") (pinfunction "2_2") (pintype "passive"))
      (node (ref "C70") (pin "2") (pinfunction "2_2") (pintype "passive"))
      (node (ref "C71") (pin "2") (pinfunction "2_2") (pintype "passive"))
      (node (ref "C72") (pin "2") (pinfunction "2_2") (pintype "passive"))
      (node (ref "C73") (pin "2") (pinfunction "2_2") (pintype "passive"))
      (node (ref "C74") (pin "2") (pinfunction "2_2") (pintype "passive"))
      (node (ref "C75") (pin "2") (pinfunction "2_2") (pintype "passive"))
      (node (ref "C76") (pin "2") (pinfunction "2_2") (pintype "passive"))
      (node (ref "C77") (pin "1") (pinfunction "1_1") (pintype "passive"))
      (node (ref "C87") (pin "1") (pinfunction "1_1") (pintype "passive"))
      (node (ref "U5") (pin "E10") (pinfunction "VDDSHV6_E10") (pintype "power_in"))
      (node (ref "U5") (pin "E11") (pinfunction "VDDSHV6_E11") (pintype "power_in"))
      (node (ref "U5") (pin "E12") (pinfunction "VDDSHV6_E12") (pintype "power_in"))
      (node (ref "U5") (pin "E13") (pinfunction "VDDSHV6_E13") (pintype "power_in"))
      (node (ref "U5") (pin "F14") (pinfunction "VDDSHV6_F14") (pintype "power_in"))
      (node (ref "U5") (pin "G14") (pinfunction "VDDSHV6_G14") (pintype "power_in"))
      (node (ref "U5") (pin "H14") (pinfunction "VDDSHV4_H14") (pintype "power_in"))
      (node (ref "U5") (pin "J14") (pinfunction "VDDSHV4_J14") (pintype "power_in"))
      (node (ref "U5") (pin "K14") (pinfunction "VDDSHV5_K14") (pintype "power_in"))
      (node (ref "U5") (pin "L14") (pinfunction "VDDSHV5_L14") (pintype "power_in"))
      (node (ref "U5") (pin "N15") (pinfunction "VDDA3P3V_USB0_N15") (pintype "power_in"))
      (node (ref "U5") (pin "N5") (pinfunction "VDDSHV6_N5") (pintype "power_in"))
      (node (ref "U5") (pin "P10") (pinfunction "VDDSHV2_P10") (pintype "power_in"))
      (node (ref "U5") (pin "P11") (pinfunction "VDDSHV2_P11") (pintype "power_in"))
      (node (ref "U5") (pin "P12") (pinfunction "VDDSHV3_P12") (pintype "power_in"))
      (node (ref "U5") (pin "P13") (pinfunction "VDDSHV3_P13") (pintype "power_in"))
      (node (ref "U5") (pin "P5") (pinfunction "VDDSHV6_P5") (pintype "power_in"))
      (node (ref "U5") (pin "P6") (pinfunction "VDDSHV6_P6") (pintype "power_in"))
      (node (ref "U5") (pin "P7") (pinfunction "VDDSHV1_P7") (pintype "power_in"))
      (node (ref "U5") (pin "P8") (pinfunction "VDDSHV1_P8") (pintype "power_in"))
      (node (ref "U5") (pin "R15") (pinfunction "VDDA3P3V_USB1_R15") (pintype "power_in"))
    )
    (net (code "14") (name "VDD_ADC") (class "Default")
      (node (ref "C93") (pin "1") (pinfunction "1_1") (pintype "passive"))
      (node (ref "FB2") (pin "1") (pinfunction "1_1") (pintype "passive"))
      (node (ref "U5") (pin "D8") (pinfunction "VDDA_ADC_D8") (pintype "power_in"))
    )
    (net (code "15") (name "VDD_CORE") (class "Default")
      (node (ref "C39") (pin "2") (pinfunction "2_2") (pintype "passive"))
      (node (ref "C40") (pin "2") (pinfunction "2_2") (pintype "passive"))
      (node (ref "C41") (pin "1") (pinfunction "1_1") (pintype "passive"))
      (node (ref "C42") (pin "1") (pinfunction "1_1") (pintype "passive"))
      (node (ref "C43") (pin "1") (pinfunction "1_1") (pintype "passive"))
      (node (ref "C44") (pin "1") (pinfunction "1_1") (pintype "passive"))
      (node (ref "C45") (pin "1") (pinfunction "1_1") (pintype "passive"))
      (node (ref "C46") (pin "1") (pinfunction "1_1") (pintype "passive"))
      (node (ref "C47") (pin "1") (pinfunction "1_1") (pintype "passive"))
      (node (ref "C48") (pin "1") (pinfunction "1_1") (pintype "passive"))
      (node (ref "C49") (pin "1") (pinfunction "1_1") (pintype "passive"))
      (node (ref "C50") (pin "1") (pinfunction "1_1") (pintype "passive"))
      (node (ref "C51") (pin "1") (pinfunction "1_1") (pintype "passive"))
      (node (ref "C52") (pin "1") (pinfunction "1_1") (pintype "passive"))
      (node (ref "C53") (pin "1") (pinfunction "1_1") (pintype "passive"))
      (node (ref "C54") (pin "1") (pinfunction "1_1") (pintype "passive"))
      (node (ref "C55") (pin "2") (pinfunction "2_2") (pintype "passive"))
      (node (ref "U5") (pin "F6") (pinfunction "VDD_CORE1_F6") (pintype "power_in"))
      (node (ref "U5") (pin "F7") (pinfunction "VDD_CORE2_F7") (pintype "power_in"))
      (node (ref "U5") (pin "G10") (pinfunction "VDD_CORE5_G10") (pintype "power_in"))
      (node (ref "U5") (pin "G6") (pinfunction "VDD_CORE3_G6") (pintype "power_in"))
      (node (ref "U5") (pin "G7") (pinfunction "VDD_CORE4_G7") (pintype "power_in"))
      (node (ref "U5") (pin "H11") (pinfunction "VDD_CORE6_H11") (pintype "power_in"))
      (node (ref "U5") (pin "J12") (pinfunction "VDD_CORE7_J12") (pintype "power_in"))
      (node (ref "U5") (pin "K12") (pinfunction "VDD_CORE10_K12") (pintype "power_in"))
      (node (ref "U5") (pin "K6") (pinfunction "VDD_CORE8_K6") (pintype "power_in"))
      (node (ref "U5") (pin "K8") (pinfunction "VDD_CORE9_K8") (pintype "power_in"))
      (node (ref "U5") (pin "L6") (pinfunction "VDD_CORE11_L6") (pintype "power_in"))
      (node (ref "U5") (pin "L7") (pinfunction "VDD_CORE12_L7") (pintype "power_in"))
      (node (ref "U5") (pin "L8") (pinfunction "VDD_CORE13_L8") (pintype "power_in"))
      (node (ref "U5") (pin "L9") (pinfunction "VDD_CORE14_L9") (pintype "power_in"))
      (node (ref "U5") (pin "M11") (pinfunction "VDD_CORE15_M11") (pintype "power_in"))
      (node (ref "U5") (pin "M13") (pinfunction "VDD_CORE16_M13") (pintype "power_in"))
      (node (ref "U5") (pin "N12") (pinfunction "VDD_CORE19_N12") (pintype "power_in"))
      (node (ref "U5") (pin "N13") (pinfunction "VDD_CORE20_N13") (pintype "power_in"))
      (node (ref "U5") (pin "N8") (pinfunction "VDD_CORE17_N8") (pintype "power_in"))
      (node (ref "U5") (pin "N9") (pinfunction "VDD_CORE18_N9") (pintype "power_in"))
    )
    (net (code "16") (name "VDD_MPU") (class "Default")
      (node (ref "C62") (pin "2") (pinfunction "2_2") (pintype "passive"))
      (node (ref "C63") (pin "1") (pinfunction "1_1") (pintype "passive"))
      (node (ref "C64") (pin "1") (pinfunction "1_1") (pintype "passive"))
      (node (ref "C65") (pin "1") (pinfunction "1_1") (pintype "passive"))
      (node (ref "U5") (pin "F10") (pinfunction "VDD_MPU1_F10") (pintype "power_in"))
      (node (ref "U5") (pin "F11") (pinfunction "VDD_MPU2_F11") (pintype "power_in"))
      (node (ref "U5") (pin "F12") (pinfunction "VDD_MPU3_F12") (pintype "power_in"))
      (node (ref "U5") (pin "F13") (pinfunction "VDD_MPU4_F13") (pintype "power_in"))
      (node (ref "U5") (pin "G13") (pinfunction "VDD_MPU5_G13") (pintype "power_in"))
      (node (ref "U5") (pin "H13") (pinfunction "VDD_MPU6_H13") (pintype "power_in"))
      (node (ref "U5") (pin "J13") (pinfunction "VDD_MPU7_J13") (pintype "power_in"))
    )
    (net (code "17") (name "VDD_PLL") (class "Default")
      (node (ref "C106") (pin "1") (pinfunction "1_1") (pintype "passive"))
      (node (ref "C79") (pin "1") (pinfunction "1_1") (pintype "passive"))
      (node (ref "C92") (pin "1") (pinfunction "1_1") (pintype "passive"))
      (node (ref "C94") (pin "1") (pinfunction "1_1") (pintype "passive"))
      (node (ref "FB1") (pin "2") (pinfunction "2_2") (pintype "passive"))
      (node (ref "U5") (pin "E7") (pinfunction "VDDS_PLL_DDR_E7") (pintype "power_in"))
      (node (ref "U5") (pin "H15") (pinfunction "VDDS_PLL_MPU_H15") (pintype "power_in"))
      (node (ref "U5") (pin "R10") (pinfunction "VDDS_PLL_CORE_LCD_R10") (pintype "power_in"))
      (node (ref "U5") (pin "R11") (pinfunction "VDDS_OSC_R11") (pintype "power_in"))
    )
    (net (code "18") (name "VRTC") (class "Default")
      (node (ref "C105") (pin "1") (pinfunction "1_1") (pintype "passive"))
      (node (ref "U5") (pin "D7") (pinfunction "VDDS_RTC_D7") (pintype "power_in"))
    )
    (net (code "19") (name "unconnected-(U5C-VPP-PadM5)") (class "Default")
      (node (ref "U5") (pin "M5") (pinfunction "VPP_M5") (pintype "power_in+no_connect"))
    )
  )
)
